# rf_frontend.net
KiCad netlist of a schematic drawn in Altium Designer
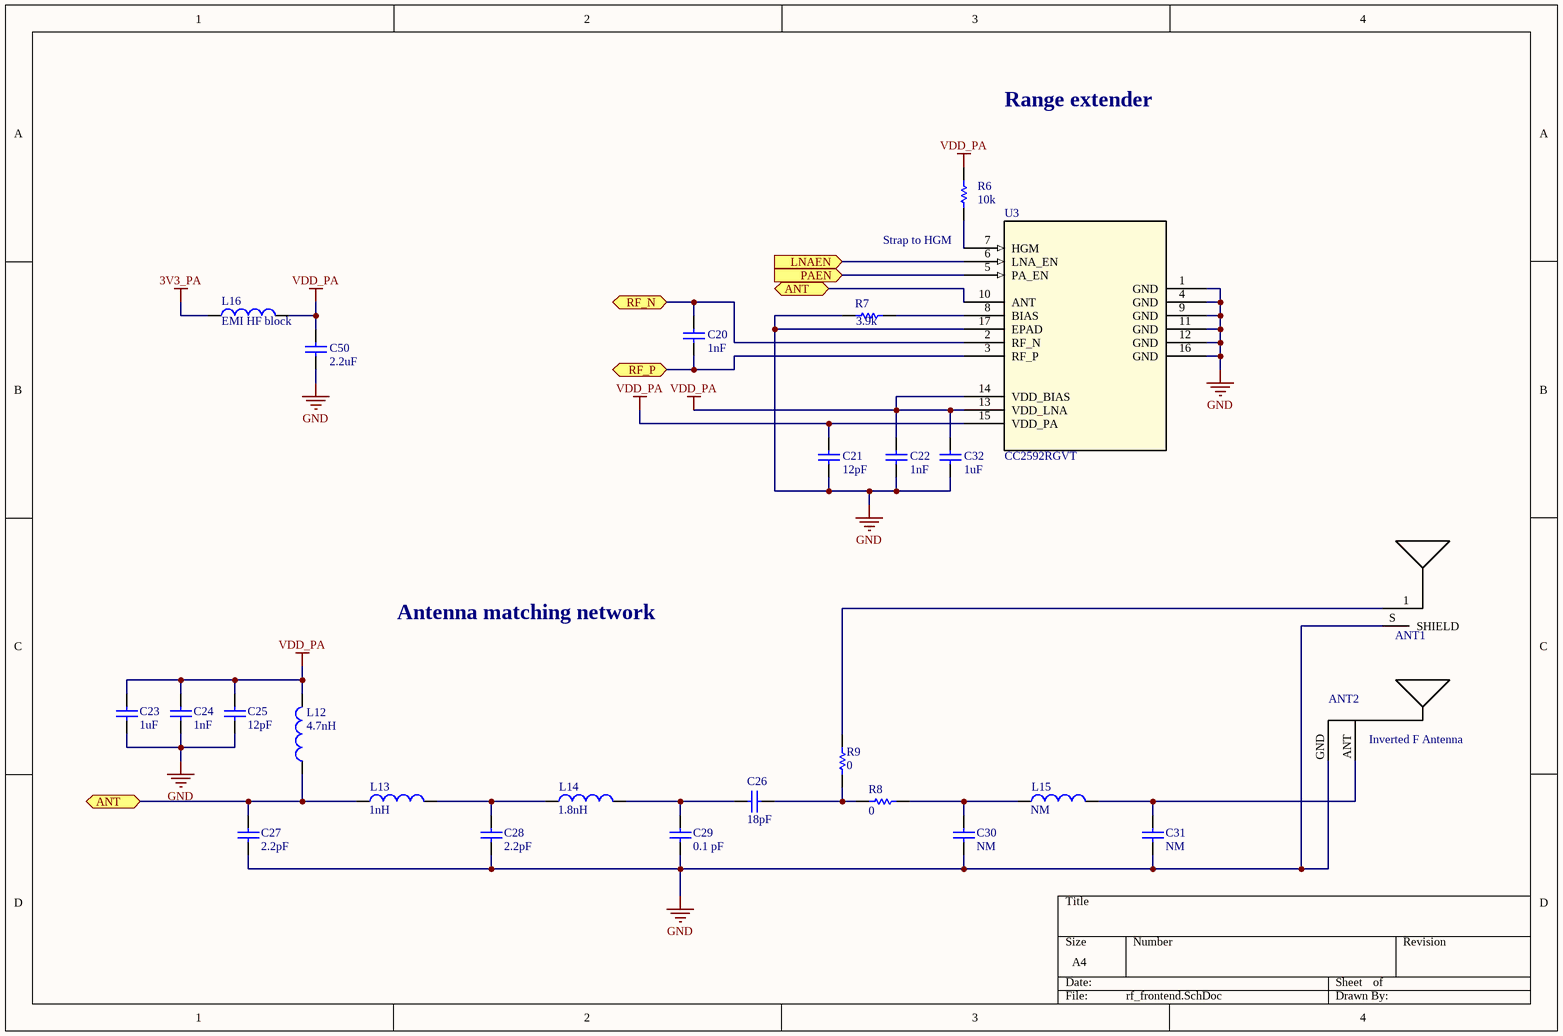
[diagram p0: rf_frontend.SchDoc]

(export (version "E")
  (design (tool "Eeschema 10.0.6"))
  (components
    (comp (ref "ANT1")
      (value "SMA RP Antenna")
      (footprint "SMA ANTENNA")
      (libsource (lib "Connectors") (part "SMA RP Antenna"))
    )
    (comp (ref "ANT2")
      (value "Inverted F ANT")
      (footprint "INVERTED_F_ANT")
      (libsource (lib "Passive Components") (part "Inverted F ANT"))
    )
    (comp (ref "C20")
      (value "1nF")
      (footprint "C_0402")
      (libsource (lib "Miscellaneous Devices") (part "Cap"))
    )
    (comp (ref "C21")
      (value "12pF")
      (footprint "C_0402")
      (libsource (lib "Miscellaneous Devices") (part "Cap"))
    )
    (comp (ref "C22")
      (value "1nF")
      (footprint "C_0402")
      (libsource (lib "Miscellaneous Devices") (part "Cap"))
    )
    (comp (ref "C23")
      (value "1uF")
      (footprint "C_0402_RF_IN_OUT")
      (libsource (lib "Miscellaneous Devices") (part "Cap"))
    )
    (comp (ref "C24")
      (value "1nF")
      (footprint "C_0402_RF_IN_OUT")
      (libsource (lib "Miscellaneous Devices") (part "Cap"))
    )
    (comp (ref "C25")
      (value "12pF")
      (footprint "C_0402_RF_IN_OUT")
      (libsource (lib "Miscellaneous Devices") (part "Cap"))
    )
    (comp (ref "C26")
      (value "18pF")
      (footprint "C_0402_RF_IN")
      (libsource (lib "Miscellaneous Devices") (part "Cap"))
    )
    (comp (ref "C27")
      (value "2.2pF")
      (footprint "C_0402_RF_IN_OUT")
      (libsource (lib "Miscellaneous Devices") (part "Cap"))
    )
    (comp (ref "C28")
      (value "2.2pF")
      (footprint "C_0402_RF_IN_OUT")
      (libsource (lib "Miscellaneous Devices") (part "Cap"))
    )
    (comp (ref "C29")
      (value "0.1 pF")
      (footprint "C_0402_RF_IN_OUT")
      (libsource (lib "Miscellaneous Devices") (part "Cap"))
    )
    (comp (ref "C30")
      (value "NM")
      (footprint "C_0402_RF_IN_OUT")
      (libsource (lib "Miscellaneous Devices") (part "Cap"))
    )
    (comp (ref "C31")
      (value "NM")
      (footprint "C_0402_RF_IN_OUT")
      (libsource (lib "Miscellaneous Devices") (part "Cap"))
    )
    (comp (ref "C32")
      (value "1uF")
      (footprint "C_0402")
      (libsource (lib "Miscellaneous Devices") (part "Cap"))
    )
    (comp (ref "C50")
      (value "2.2uF")
      (footprint "C_0402")
      (libsource (lib "Miscellaneous Devices") (part "Cap"))
    )
    (comp (ref "L12")
      (value "4.7nH")
      (footprint "R_0402_IN_OUT")
      (fields (field (name "Comment") "Inductor"))
      (libsource (lib "Miscellaneous Devices") (part "Inductor"))
    )
    (comp (ref "L13")
      (value "1nH")
      (footprint "L_0402_RF_IN")
      (fields (field (name "Comment") "Inductor"))
      (libsource (lib "Miscellaneous Devices") (part "Inductor"))
    )
    (comp (ref "L14")
      (value "1.8nH")
      (footprint "L_0402_RF_IN")
      (fields (field (name "Comment") "Inductor"))
      (libsource (lib "Miscellaneous Devices") (part "Inductor"))
    )
    (comp (ref "L15")
      (value "NM")
      (footprint "L_0402_RF_IN")
      (fields (field (name "Comment") "Inductor"))
      (libsource (lib "Miscellaneous Devices") (part "Inductor"))
    )
    (comp (ref "L16")
      (value "EMI HF block")
      (footprint "L_0402")
      (fields (field (name "Comment") "Inductor"))
      (libsource (lib "Miscellaneous Devices") (part "Inductor"))
    )
    (comp (ref "R6")
      (value "10k")
      (footprint "R_0402")
      (description "Resistor")
      (fields (field (name "Comment") "Res1"))
      (libsource (lib "Miscellaneous Devices") (part "Res1"))
    )
    (comp (ref "R7")
      (value "3.9k")
      (footprint "R_0402")
      (description "Resistor")
      (fields (field (name "Comment") "Res1"))
      (libsource (lib "Miscellaneous Devices") (part "Res1"))
    )
    (comp (ref "R8")
      (value "0")
      (footprint "R_0402_IN_OUT")
      (description "Resistor")
      (fields (field (name "Comment") "Res1"))
      (libsource (lib "Miscellaneous Devices") (part "Res1"))
    )
    (comp (ref "R9")
      (value "0")
      (footprint "R_0402_IN")
      (description "Resistor")
      (fields (field (name "Comment") "Res1"))
      (libsource (lib "Miscellaneous Devices") (part "Res1"))
    )
    (comp (ref "U3")
      (value "CC2592RGVT")
      (footprint "RGV16_2P16X2P16")
      (description "Imported")
      (libsource (lib "CC2592") (part "CC2592RGVT"))
    )
  )
  (nets
    (net (code "1") (name "/ANT") (class "Default")
      (node (ref "C27") (pin "1") (pinfunction "1_1") (pintype "passive"))
      (node (ref "L12") (pin "1") (pinfunction "1_1") (pintype "passive"))
      (node (ref "L13") (pin "1") (pinfunction "1_1") (pintype "passive"))
      (node (ref "U3") (pin "10") (pinfunction "ANT_10") (pintype "passive"))
    )
    (net (code "2") (name "/LNAEN") (class "Default")
      (node (ref "U3") (pin "6") (pinfunction "LNA_EN_6") (pintype "input"))
    )
    (net (code "3") (name "/PAEN") (class "Default")
      (node (ref "U3") (pin "5") (pinfunction "PA_EN_5") (pintype "input"))
    )
    (net (code "4") (name "/RF_N") (class "Default")
      (node (ref "C20") (pin "2") (pinfunction "2_2") (pintype "passive"))
      (node (ref "U3") (pin "2") (pinfunction "RF_N_2") (pintype "passive"))
    )
    (net (code "5") (name "/RF_P") (class "Default")
      (node (ref "C20") (pin "1") (pinfunction "1_1") (pintype "passive"))
      (node (ref "U3") (pin "3") (pinfunction "RF_P_3") (pintype "passive"))
    )
    (net (code "6") (name "3V3_PA") (class "Default")
      (node (ref "L16") (pin "1") (pinfunction "1_1") (pintype "passive"))
    )
    (net (code "7") (name "GND") (class "Default")
      (node (ref "ANT1") (pin "S") (pinfunction "SHIELD_S") (pintype "passive"))
      (node (ref "ANT2") (pin "GND") (pinfunction "GND_GND") (pintype "passive"))
      (node (ref "C21") (pin "1") (pinfunction "1_1") (pintype "passive"))
      (node (ref "C22") (pin "1") (pinfunction "1_1") (pintype "passive"))
      (node (ref "C23") (pin "2") (pinfunction "2_2") (pintype "passive"))
      (node (ref "C24") (pin "2") (pinfunction "2_2") (pintype "passive"))
      (node (ref "C25") (pin "2") (pinfunction "2_2") (pintype "passive"))
      (node (ref "C27") (pin "2") (pinfunction "2_2") (pintype "passive"))
      (node (ref "C28") (pin "2") (pinfunction "2_2") (pintype "passive"))
      (node (ref "C29") (pin "2") (pinfunction "2_2") (pintype "passive"))
      (node (ref "C30") (pin "2") (pinfunction "2_2") (pintype "passive"))
      (node (ref "C31") (pin "2") (pinfunction "2_2") (pintype "passive"))
      (node (ref "C32") (pin "1") (pinfunction "1_1") (pintype "passive"))
      (node (ref "C50") (pin "1") (pinfunction "1_1") (pintype "passive"))
      (node (ref "R7") (pin "2") (pinfunction "2_2") (pintype "passive"))
      (node (ref "U3") (pin "1") (pinfunction "GND_1") (pintype "power_in"))
      (node (ref "U3") (pin "11") (pinfunction "GND_11") (pintype "power_in"))
      (node (ref "U3") (pin "12") (pinfunction "GND_12") (pintype "power_in"))
      (node (ref "U3") (pin "16") (pinfunction "GND_16") (pintype "power_in"))
      (node (ref "U3") (pin "17") (pinfunction "EPAD_17") (pintype "passive"))
      (node (ref "U3") (pin "4") (pinfunction "GND_4") (pintype "power_in"))
      (node (ref "U3") (pin "9") (pinfunction "GND_9") (pintype "power_in"))
    )
    (net (code "8") (name "Net-(ANT1-FEED)") (class "Default")
      (node (ref "ANT1") (pin "1") (pinfunction "FEED_1") (pintype "passive"))
      (node (ref "R9") (pin "1") (pinfunction "1_1") (pintype "passive"))
    )
    (net (code "9") (name "Net-(ANT2-PadANT)") (class "Default")
      (node (ref "ANT2") (pin "ANT") (pinfunction "ANT_ANT") (pintype "passive"))
      (node (ref "C31") (pin "1") (pinfunction "1_1") (pintype "passive"))
      (node (ref "L15") (pin "2") (pinfunction "2_2") (pintype "passive"))
    )
    (net (code "10") (name "Net-(C26-Pad1)") (class "Default")
      (node (ref "C26") (pin "1") (pinfunction "1_1") (pintype "passive"))
      (node (ref "R8") (pin "1") (pinfunction "1_1") (pintype "passive"))
      (node (ref "R9") (pin "2") (pinfunction "2_2") (pintype "passive"))
    )
    (net (code "11") (name "Net-(C26-Pad2)") (class "Default")
      (node (ref "C26") (pin "2") (pinfunction "2_2") (pintype "passive"))
      (node (ref "C29") (pin "1") (pinfunction "1_1") (pintype "passive"))
      (node (ref "L14") (pin "2") (pinfunction "2_2") (pintype "passive"))
    )
    (net (code "12") (name "Net-(C28-Pad1)") (class "Default")
      (node (ref "C28") (pin "1") (pinfunction "1_1") (pintype "passive"))
      (node (ref "L13") (pin "2") (pinfunction "2_2") (pintype "passive"))
      (node (ref "L14") (pin "1") (pinfunction "1_1") (pintype "passive"))
    )
    (net (code "13") (name "Net-(C30-Pad1)") (class "Default")
      (node (ref "C30") (pin "1") (pinfunction "1_1") (pintype "passive"))
      (node (ref "L15") (pin "1") (pinfunction "1_1") (pintype "passive"))
      (node (ref "R8") (pin "2") (pinfunction "2_2") (pintype "passive"))
    )
    (net (code "14") (name "Net-(U3-BIAS)") (class "Default")
      (node (ref "R7") (pin "1") (pinfunction "1_1") (pintype "passive"))
      (node (ref "U3") (pin "8") (pinfunction "BIAS_8") (pintype "passive"))
    )
    (net (code "15") (name "Net-(U3-HGM)") (class "Default")
      (node (ref "R6") (pin "1") (pinfunction "1_1") (pintype "passive"))
      (node (ref "U3") (pin "7") (pinfunction "HGM_7") (pintype "input"))
    )
    (net (code "16") (name "VDD_PA") (class "Default")
      (node (ref "C21") (pin "2") (pinfunction "2_2") (pintype "passive"))
      (node (ref "C22") (pin "2") (pinfunction "2_2") (pintype "passive"))
      (node (ref "C23") (pin "1") (pinfunction "1_1") (pintype "passive"))
      (node (ref "C24") (pin "1") (pinfunction "1_1") (pintype "passive"))
      (node (ref "C25") (pin "1") (pinfunction "1_1") (pintype "passive"))
      (node (ref "C32") (pin "2") (pinfunction "2_2") (pintype "passive"))
      (node (ref "C50") (pin "2") (pinfunction "2_2") (pintype "passive"))
      (node (ref "L12") (pin "2") (pinfunction "2_2") (pintype "passive"))
      (node (ref "L16") (pin "2") (pinfunction "2_2") (pintype "passive"))
      (node (ref "R6") (pin "2") (pinfunction "2_2") (pintype "passive"))
      (node (ref "U3") (pin "13") (pinfunction "VDD_LNA_13") (pintype "power_in"))
      (node (ref "U3") (pin "14") (pinfunction "VDD_BIAS_14") (pintype "power_in"))
      (node (ref "U3") (pin "15") (pinfunction "VDD_PA_15") (pintype "power_in"))
    )
  )
)
